# 3phase-boiler-controller-arduino.net
KiCad netlist of a schematic drawn in EAGLE
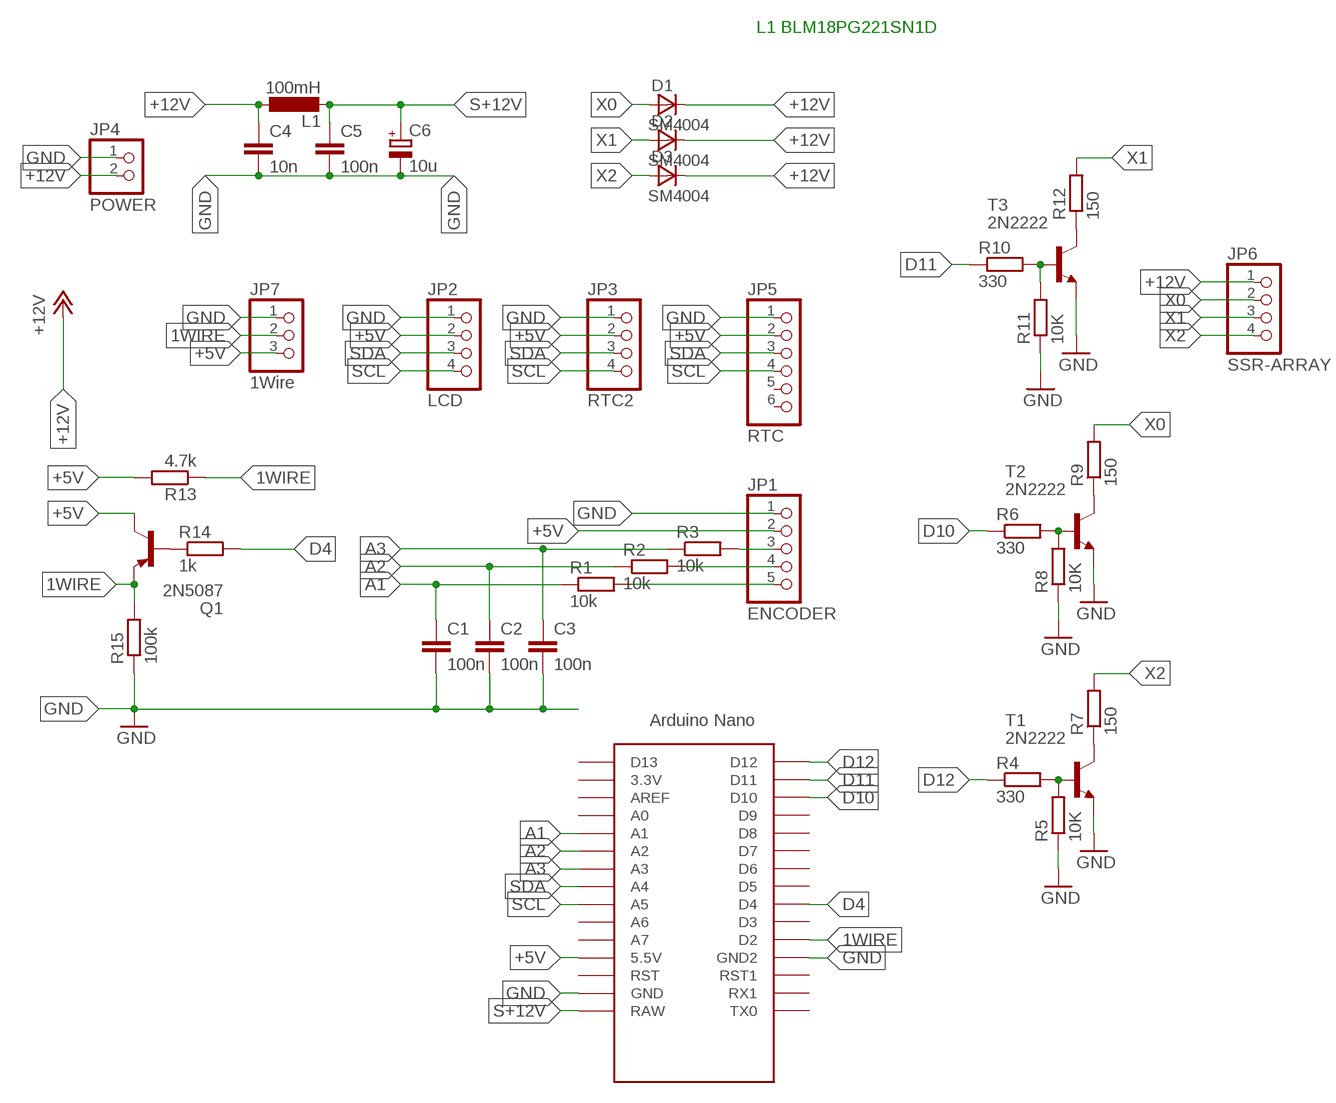
[diagram p0: schematic, sheet 1]

(export (version "E")
  (design (tool "Eeschema 10.0.6"))
  (components
    (comp (ref "C1")
      (value "100n")
      (footprint "eagle-import:C0603")
      (fields (field (name "SPICEPREFIX") "C"))
      (libsource (lib "eagle-import") (part "C-EUC0603"))
    )
    (comp (ref "C2")
      (value "100n")
      (footprint "eagle-import:C0603")
      (libsource (lib "eagle-import") (part "C-EUC0603"))
    )
    (comp (ref "C3")
      (value "100n")
      (footprint "eagle-import:C0603")
      (libsource (lib "eagle-import") (part "C-EUC0603"))
    )
    (comp (ref "C4")
      (value "10n")
      (footprint "eagle-import:C0603")
      (libsource (lib "eagle-import") (part "C-EUC0603"))
    )
    (comp (ref "C5")
      (value "100n")
      (footprint "eagle-import:C0603")
      (libsource (lib "eagle-import") (part "C-EUC0603"))
    )
    (comp (ref "C6")
      (value "10u")
      (footprint "eagle-import:153CLV-0807")
      (libsource (lib "eagle-import") (part "CPOL-EU153CLV-0807"))
    )
    (comp (ref "D1")
      (value "SM4004")
      (footprint "eagle-import:MELF-MLL41")
      (libsource (lib "eagle-import") (part "SM4004"))
    )
    (comp (ref "D2")
      (value "SM4004")
      (footprint "eagle-import:MELF-MLL41")
      (libsource (lib "eagle-import") (part "SM4004"))
    )
    (comp (ref "D3")
      (value "SM4004")
      (footprint "eagle-import:MELF-MLL41")
      (libsource (lib "eagle-import") (part "SM4004"))
    )
    (comp (ref "JP1")
      (value "ENCODER")
      (footprint "eagle-import:1X05")
      (libsource (lib "eagle-import") (part "PINHD-1X5"))
    )
    (comp (ref "JP2")
      (value "LCD")
      (footprint "eagle-import:1X04")
      (libsource (lib "eagle-import") (part "PINHD-1X4"))
    )
    (comp (ref "JP3")
      (value "RTC2")
      (footprint "eagle-import:1X04")
      (libsource (lib "eagle-import") (part "PINHD-1X4"))
    )
    (comp (ref "JP4")
      (value "POWER")
      (footprint "eagle-import:1X02")
      (libsource (lib "eagle-import") (part "PINHD-1X2"))
    )
    (comp (ref "JP5")
      (value "RTC")
      (footprint "eagle-import:1X06_90")
      (libsource (lib "eagle-import") (part "PINHD-1X6/90"))
    )
    (comp (ref "JP6")
      (value "SSR-ARRAY")
      (footprint "eagle-import:1X04")
      (libsource (lib "eagle-import") (part "PINHD-1X4"))
    )
    (comp (ref "JP7")
      (value "1Wire")
      (footprint "eagle-import:1X03")
      (libsource (lib "eagle-import") (part "PINHD-1X3"))
    )
    (comp (ref "L1")
      (value "100mH")
      (footprint "eagle-import:0207_12")
      (libsource (lib "eagle-import") (part "L-EU0207/12"))
    )
    (comp (ref "Q1")
      (value "2N5087")
      (footprint "eagle-import:TO92")
      (libsource (lib "eagle-import") (part "2N5087"))
    )
    (comp (ref "R1")
      (value "10k")
      (footprint "eagle-import:R0805")
      (libsource (lib "eagle-import") (part "R-EU_R0805"))
    )
    (comp (ref "R2")
      (value "10k")
      (footprint "eagle-import:R0805")
      (libsource (lib "eagle-import") (part "R-EU_R0805"))
    )
    (comp (ref "R3")
      (value "10k")
      (footprint "eagle-import:R0805")
      (libsource (lib "eagle-import") (part "R-EU_R0805"))
    )
    (comp (ref "R4")
      (value "330")
      (footprint "eagle-import:R0805")
      (libsource (lib "eagle-import") (part "R-EU_R0805"))
    )
    (comp (ref "R5")
      (value "10K")
      (footprint "eagle-import:R0805")
      (libsource (lib "eagle-import") (part "R-EU_R0805"))
    )
    (comp (ref "R6")
      (value "330")
      (footprint "eagle-import:R0805")
      (libsource (lib "eagle-import") (part "R-EU_R0805"))
    )
    (comp (ref "R7")
      (value "150")
      (footprint "eagle-import:R0805")
      (libsource (lib "eagle-import") (part "R-EU_R0805"))
    )
    (comp (ref "R8")
      (value "10K")
      (footprint "eagle-import:R0805")
      (libsource (lib "eagle-import") (part "R-EU_R0805"))
    )
    (comp (ref "R9")
      (value "150")
      (footprint "eagle-import:R0805")
      (libsource (lib "eagle-import") (part "R-EU_R0805"))
    )
    (comp (ref "R10")
      (value "330")
      (footprint "eagle-import:R0805")
      (libsource (lib "eagle-import") (part "R-EU_R0805"))
    )
    (comp (ref "R11")
      (value "10K")
      (footprint "eagle-import:R0805")
      (libsource (lib "eagle-import") (part "R-EU_R0805"))
    )
    (comp (ref "R12")
      (value "150")
      (footprint "eagle-import:R0805")
      (libsource (lib "eagle-import") (part "R-EU_R0805"))
    )
    (comp (ref "R13")
      (value "4.7k")
      (footprint "eagle-import:R0805")
      (libsource (lib "eagle-import") (part "resistor_R-EU_R0805"))
    )
    (comp (ref "R14")
      (value "1k")
      (footprint "eagle-import:R0805")
      (libsource (lib "eagle-import") (part "R-EU_R0805"))
    )
    (comp (ref "R15")
      (value "100k")
      (footprint "eagle-import:R0805")
      (libsource (lib "eagle-import") (part "R-EU_R0805"))
    )
    (comp (ref "T1")
      (value "2N2222")
      (footprint "eagle-import:TO92-EBC-OVAL")
      (libsource (lib "eagle-import") (part "2N2222"))
    )
    (comp (ref "T2")
      (value "2N2222")
      (footprint "eagle-import:TO92-EBC-OVAL")
      (libsource (lib "eagle-import") (part "2N2222"))
    )
    (comp (ref "T3")
      (value "2N2222")
      (footprint "eagle-import:TO92-EBC-OVAL")
      (libsource (lib "eagle-import") (part "2N2222"))
    )
    (comp (ref "U$1")
      (value "NANO")
      (footprint "eagle-import:NANO")
      (libsource (lib "eagle-import") (part "NANO"))
    )
  )
  (nets
    (net (code "1") (name "+5V") (class "Default")
      (node (ref "JP1") (pin "2") (pinfunction "2_2") (pintype "passive"))
      (node (ref "JP2") (pin "2") (pinfunction "2_2") (pintype "passive"))
      (node (ref "JP3") (pin "2") (pinfunction "2_2") (pintype "passive"))
      (node (ref "JP5") (pin "2") (pinfunction "2_2") (pintype "passive"))
      (node (ref "JP7") (pin "3") (pinfunction "3_3") (pintype "passive"))
      (node (ref "Q1") (pin "1") (pinfunction "C_1") (pintype "passive"))
      (node (ref "R13") (pin "2") (pinfunction "2_2") (pintype "passive"))
      (node (ref "U$1") (pin "5V") (pinfunction "5.5V_5V") (pintype "bidirectional"))
    )
    (net (code "2") (name "+12V") (class "Default")
      (node (ref "C4") (pin "1") (pinfunction "1_1") (pintype "passive"))
      (node (ref "D1") (pin "C") (pinfunction "C_C") (pintype "passive"))
      (node (ref "D2") (pin "C") (pinfunction "C_C") (pintype "passive"))
      (node (ref "D3") (pin "C") (pinfunction "C_C") (pintype "passive"))
      (node (ref "JP4") (pin "2") (pinfunction "2_2") (pintype "passive"))
      (node (ref "JP6") (pin "1") (pinfunction "1_1") (pintype "passive"))
      (node (ref "L1") (pin "1") (pinfunction "1_1") (pintype "passive"))
    )
    (net (code "3") (name "1WIRE") (class "Default")
      (node (ref "JP7") (pin "2") (pinfunction "2_2") (pintype "passive"))
      (node (ref "Q1") (pin "3") (pinfunction "E_3") (pintype "passive"))
      (node (ref "R13") (pin "1") (pinfunction "1_1") (pintype "passive"))
      (node (ref "R15") (pin "2") (pinfunction "2_2") (pintype "passive"))
      (node (ref "U$1") (pin "D2") (pinfunction "D2_D2") (pintype "bidirectional"))
    )
    (net (code "4") (name "A1") (class "Default")
      (node (ref "C1") (pin "1") (pinfunction "1_1") (pintype "passive"))
      (node (ref "R1") (pin "1") (pinfunction "1_1") (pintype "passive"))
      (node (ref "U$1") (pin "A1") (pinfunction "A1_A1") (pintype "bidirectional"))
    )
    (net (code "5") (name "A2") (class "Default")
      (node (ref "C2") (pin "1") (pinfunction "1_1") (pintype "passive"))
      (node (ref "R2") (pin "1") (pinfunction "1_1") (pintype "passive"))
      (node (ref "U$1") (pin "A2") (pinfunction "A2_A2") (pintype "bidirectional"))
    )
    (net (code "6") (name "A3") (class "Default")
      (node (ref "C3") (pin "1") (pinfunction "1_1") (pintype "passive"))
      (node (ref "R3") (pin "1") (pinfunction "1_1") (pintype "passive"))
      (node (ref "U$1") (pin "A3") (pinfunction "A3_A3") (pintype "bidirectional"))
    )
    (net (code "7") (name "D4") (class "Default")
      (node (ref "R14") (pin "2") (pinfunction "2_2") (pintype "passive"))
      (node (ref "U$1") (pin "D4") (pinfunction "D4_D4") (pintype "bidirectional"))
    )
    (net (code "8") (name "D10") (class "Default")
      (node (ref "R6") (pin "1") (pinfunction "1_1") (pintype "passive"))
      (node (ref "U$1") (pin "D10") (pinfunction "D10_D10") (pintype "bidirectional"))
    )
    (net (code "9") (name "D11") (class "Default")
      (node (ref "R10") (pin "1") (pinfunction "1_1") (pintype "passive"))
      (node (ref "U$1") (pin "D11") (pinfunction "D11_D11") (pintype "bidirectional"))
    )
    (net (code "10") (name "D12") (class "Default")
      (node (ref "R4") (pin "1") (pinfunction "1_1") (pintype "passive"))
      (node (ref "U$1") (pin "D12") (pinfunction "D12_D12") (pintype "bidirectional"))
    )
    (net (code "11") (name "GND") (class "Default")
      (node (ref "C1") (pin "2") (pinfunction "2_2") (pintype "passive"))
      (node (ref "C2") (pin "2") (pinfunction "2_2") (pintype "passive"))
      (node (ref "C3") (pin "2") (pinfunction "2_2") (pintype "passive"))
      (node (ref "C4") (pin "2") (pinfunction "2_2") (pintype "passive"))
      (node (ref "C5") (pin "2") (pinfunction "2_2") (pintype "passive"))
      (node (ref "C6") (pin "-") (pinfunction "-_-") (pintype "passive"))
      (node (ref "JP1") (pin "1") (pinfunction "1_1") (pintype "passive"))
      (node (ref "JP2") (pin "1") (pinfunction "1_1") (pintype "passive"))
      (node (ref "JP3") (pin "1") (pinfunction "1_1") (pintype "passive"))
      (node (ref "JP4") (pin "1") (pinfunction "1_1") (pintype "passive"))
      (node (ref "JP5") (pin "1") (pinfunction "1_1") (pintype "passive"))
      (node (ref "JP7") (pin "1") (pinfunction "1_1") (pintype "passive"))
      (node (ref "R11") (pin "1") (pinfunction "1_1") (pintype "passive"))
      (node (ref "R15") (pin "1") (pinfunction "1_1") (pintype "passive"))
      (node (ref "R5") (pin "1") (pinfunction "1_1") (pintype "passive"))
      (node (ref "R8") (pin "1") (pinfunction "1_1") (pintype "passive"))
      (node (ref "T1") (pin "E") (pinfunction "E_E") (pintype "passive"))
      (node (ref "T2") (pin "E") (pinfunction "E_E") (pintype "passive"))
      (node (ref "T3") (pin "E") (pinfunction "E_E") (pintype "passive"))
      (node (ref "U$1") (pin "GND") (pinfunction "GND_GND") (pintype "bidirectional"))
      (node (ref "U$1") (pin "GND1") (pinfunction "GND2_GND1") (pintype "bidirectional"))
    )
    (net (code "12") (name "Net-(JP1-Pad3)") (class "Default")
      (node (ref "JP1") (pin "3") (pinfunction "3_3") (pintype "passive"))
      (node (ref "R3") (pin "2") (pinfunction "2_2") (pintype "passive"))
    )
    (net (code "13") (name "Net-(JP1-Pad4)") (class "Default")
      (node (ref "JP1") (pin "4") (pinfunction "4_4") (pintype "passive"))
      (node (ref "R2") (pin "2") (pinfunction "2_2") (pintype "passive"))
    )
    (net (code "14") (name "Net-(JP1-Pad5)") (class "Default")
      (node (ref "JP1") (pin "5") (pinfunction "5_5") (pintype "passive"))
      (node (ref "R1") (pin "2") (pinfunction "2_2") (pintype "passive"))
    )
    (net (code "15") (name "Net-(Q1-B)") (class "Default")
      (node (ref "Q1") (pin "2") (pinfunction "B_2") (pintype "passive"))
      (node (ref "R14") (pin "1") (pinfunction "1_1") (pintype "passive"))
    )
    (net (code "16") (name "Net-(R4-Pad2)") (class "Default")
      (node (ref "R4") (pin "2") (pinfunction "2_2") (pintype "passive"))
      (node (ref "R5") (pin "2") (pinfunction "2_2") (pintype "passive"))
      (node (ref "T1") (pin "B") (pinfunction "B_B") (pintype "passive"))
    )
    (net (code "17") (name "Net-(R6-Pad2)") (class "Default")
      (node (ref "R6") (pin "2") (pinfunction "2_2") (pintype "passive"))
      (node (ref "R8") (pin "2") (pinfunction "2_2") (pintype "passive"))
      (node (ref "T2") (pin "B") (pinfunction "B_B") (pintype "passive"))
    )
    (net (code "18") (name "Net-(R7-Pad1)") (class "Default")
      (node (ref "R7") (pin "1") (pinfunction "1_1") (pintype "passive"))
      (node (ref "T1") (pin "C") (pinfunction "C_C") (pintype "passive"))
    )
    (net (code "19") (name "Net-(R9-Pad1)") (class "Default")
      (node (ref "R9") (pin "1") (pinfunction "1_1") (pintype "passive"))
      (node (ref "T2") (pin "C") (pinfunction "C_C") (pintype "passive"))
    )
    (net (code "20") (name "Net-(R10-Pad2)") (class "Default")
      (node (ref "R10") (pin "2") (pinfunction "2_2") (pintype "passive"))
      (node (ref "R11") (pin "2") (pinfunction "2_2") (pintype "passive"))
      (node (ref "T3") (pin "B") (pinfunction "B_B") (pintype "passive"))
    )
    (net (code "21") (name "Net-(R12-Pad1)") (class "Default")
      (node (ref "R12") (pin "1") (pinfunction "1_1") (pintype "passive"))
      (node (ref "T3") (pin "C") (pinfunction "C_C") (pintype "passive"))
    )
    (net (code "22") (name "S+12V") (class "Default")
      (node (ref "C5") (pin "1") (pinfunction "1_1") (pintype "passive"))
      (node (ref "C6") (pin "+") (pinfunction "+_+") (pintype "passive"))
      (node (ref "L1") (pin "2") (pinfunction "2_2") (pintype "passive"))
      (node (ref "U$1") (pin "RAW") (pinfunction "RAW_RAW") (pintype "bidirectional"))
    )
    (net (code "23") (name "SCL") (class "Default")
      (node (ref "JP2") (pin "4") (pinfunction "4_4") (pintype "passive"))
      (node (ref "JP3") (pin "4") (pinfunction "4_4") (pintype "passive"))
      (node (ref "JP5") (pin "4") (pinfunction "4_4") (pintype "passive"))
      (node (ref "U$1") (pin "A5") (pinfunction "A5_A5") (pintype "bidirectional"))
    )
    (net (code "24") (name "SDA") (class "Default")
      (node (ref "JP2") (pin "3") (pinfunction "3_3") (pintype "passive"))
      (node (ref "JP3") (pin "3") (pinfunction "3_3") (pintype "passive"))
      (node (ref "JP5") (pin "3") (pinfunction "3_3") (pintype "passive"))
      (node (ref "U$1") (pin "A4") (pinfunction "A4_A4") (pintype "bidirectional"))
    )
    (net (code "25") (name "X0") (class "Default")
      (node (ref "D1") (pin "A") (pinfunction "A_A") (pintype "passive"))
      (node (ref "JP6") (pin "2") (pinfunction "2_2") (pintype "passive"))
      (node (ref "R9") (pin "2") (pinfunction "2_2") (pintype "passive"))
    )
    (net (code "26") (name "X1") (class "Default")
      (node (ref "D2") (pin "A") (pinfunction "A_A") (pintype "passive"))
      (node (ref "JP6") (pin "3") (pinfunction "3_3") (pintype "passive"))
      (node (ref "R12") (pin "2") (pinfunction "2_2") (pintype "passive"))
    )
    (net (code "27") (name "X2") (class "Default")
      (node (ref "D3") (pin "A") (pinfunction "A_A") (pintype "passive"))
      (node (ref "JP6") (pin "4") (pinfunction "4_4") (pintype "passive"))
      (node (ref "R7") (pin "2") (pinfunction "2_2") (pintype "passive"))
    )
    (net (code "28") (name "unconnected-(JP5-Pad5)") (class "Default")
      (node (ref "JP5") (pin "5") (pinfunction "5_5") (pintype "passive"))
    )
    (net (code "29") (name "unconnected-(JP5-Pad6)") (class "Default")
      (node (ref "JP5") (pin "6") (pinfunction "6_6") (pintype "passive"))
    )
    (net (code "30") (name "unconnected-(U$1-Pad3.3V)") (class "Default")
      (node (ref "U$1") (pin "3.3V") (pinfunction "3.3V_3.3V") (pintype "bidirectional"))
    )
    (net (code "31") (name "unconnected-(U$1-PadA0)") (class "Default")
      (node (ref "U$1") (pin "A0") (pinfunction "A0_A0") (pintype "bidirectional"))
    )
    (net (code "32") (name "unconnected-(U$1-PadA6)") (class "Default")
      (node (ref "U$1") (pin "A6") (pinfunction "A6_A6") (pintype "bidirectional"))
    )
    (net (code "33") (name "unconnected-(U$1-PadA7)") (class "Default")
      (node (ref "U$1") (pin "A7") (pinfunction "A7_A7") (pintype "bidirectional"))
    )
    (net (code "34") (name "unconnected-(U$1-PadAREF)") (class "Default")
      (node (ref "U$1") (pin "AREF") (pinfunction "AREF_AREF") (pintype "bidirectional"))
    )
    (net (code "35") (name "unconnected-(U$1-PadD3)") (class "Default")
      (node (ref "U$1") (pin "D3") (pinfunction "D3_D3") (pintype "bidirectional"))
    )
    (net (code "36") (name "unconnected-(U$1-PadD5)") (class "Default")
      (node (ref "U$1") (pin "D5") (pinfunction "D5_D5") (pintype "bidirectional"))
    )
    (net (code "37") (name "unconnected-(U$1-PadD6)") (class "Default")
      (node (ref "U$1") (pin "D6") (pinfunction "D6_D6") (pintype "bidirectional"))
    )
    (net (code "38") (name "unconnected-(U$1-PadD7)") (class "Default")
      (node (ref "U$1") (pin "D7") (pinfunction "D7_D7") (pintype "bidirectional"))
    )
    (net (code "39") (name "unconnected-(U$1-PadD8)") (class "Default")
      (node (ref "U$1") (pin "D8") (pinfunction "D8_D8") (pintype "bidirectional"))
    )
    (net (code "40") (name "unconnected-(U$1-PadD9)") (class "Default")
      (node (ref "U$1") (pin "D9") (pinfunction "D9_D9") (pintype "bidirectional"))
    )
    (net (code "41") (name "unconnected-(U$1-PadD13)") (class "Default")
      (node (ref "U$1") (pin "D13") (pinfunction "D13_D13") (pintype "bidirectional"))
    )
    (net (code "42") (name "unconnected-(U$1-PadICSP1)") (class "Default")
      (node (ref "U$1") (pin "ICSP1") (pinfunction "ICSP1_ICSP1") (pintype "bidirectional"))
    )
    (net (code "43") (name "unconnected-(U$1-PadICSP2)") (class "Default")
      (node (ref "U$1") (pin "ICSP2") (pinfunction "ICSP2_ICSP2") (pintype "bidirectional"))
    )
    (net (code "44") (name "unconnected-(U$1-PadICSP3)") (class "Default")
      (node (ref "U$1") (pin "ICSP3") (pinfunction "ICSP3_ICSP3") (pintype "bidirectional"))
    )
    (net (code "45") (name "unconnected-(U$1-PadICSP4)") (class "Default")
      (node (ref "U$1") (pin "ICSP4") (pinfunction "ICSP4_ICSP4") (pintype "bidirectional"))
    )
    (net (code "46") (name "unconnected-(U$1-PadICSP5)") (class "Default")
      (node (ref "U$1") (pin "ICSP5") (pinfunction "ICSP5_ICSP5") (pintype "bidirectional"))
    )
    (net (code "47") (name "unconnected-(U$1-PadICSP6)") (class "Default")
      (node (ref "U$1") (pin "ICSP6") (pinfunction "ICSP6_ICSP6") (pintype "bidirectional"))
    )
    (net (code "48") (name "unconnected-(U$1-PadRST)") (class "Default")
      (node (ref "U$1") (pin "RST") (pinfunction "RST_RST") (pintype "bidirectional"))
    )
    (net (code "49") (name "unconnected-(U$1-PadRST1)") (class "Default")
      (node (ref "U$1") (pin "RST1") (pinfunction "RST1_RST1") (pintype "bidirectional"))
    )
    (net (code "50") (name "unconnected-(U$1-PadRX1)") (class "Default")
      (node (ref "U$1") (pin "RX1") (pinfunction "RX1_RX1") (pintype "bidirectional"))
    )
    (net (code "51") (name "unconnected-(U$1-PadTX0)") (class "Default")
      (node (ref "U$1") (pin "TX0") (pinfunction "TX0_TX0") (pintype "bidirectional"))
    )
  )
)
